# FeederShieldMega.net
KiCad netlist of a schematic drawn in EAGLE
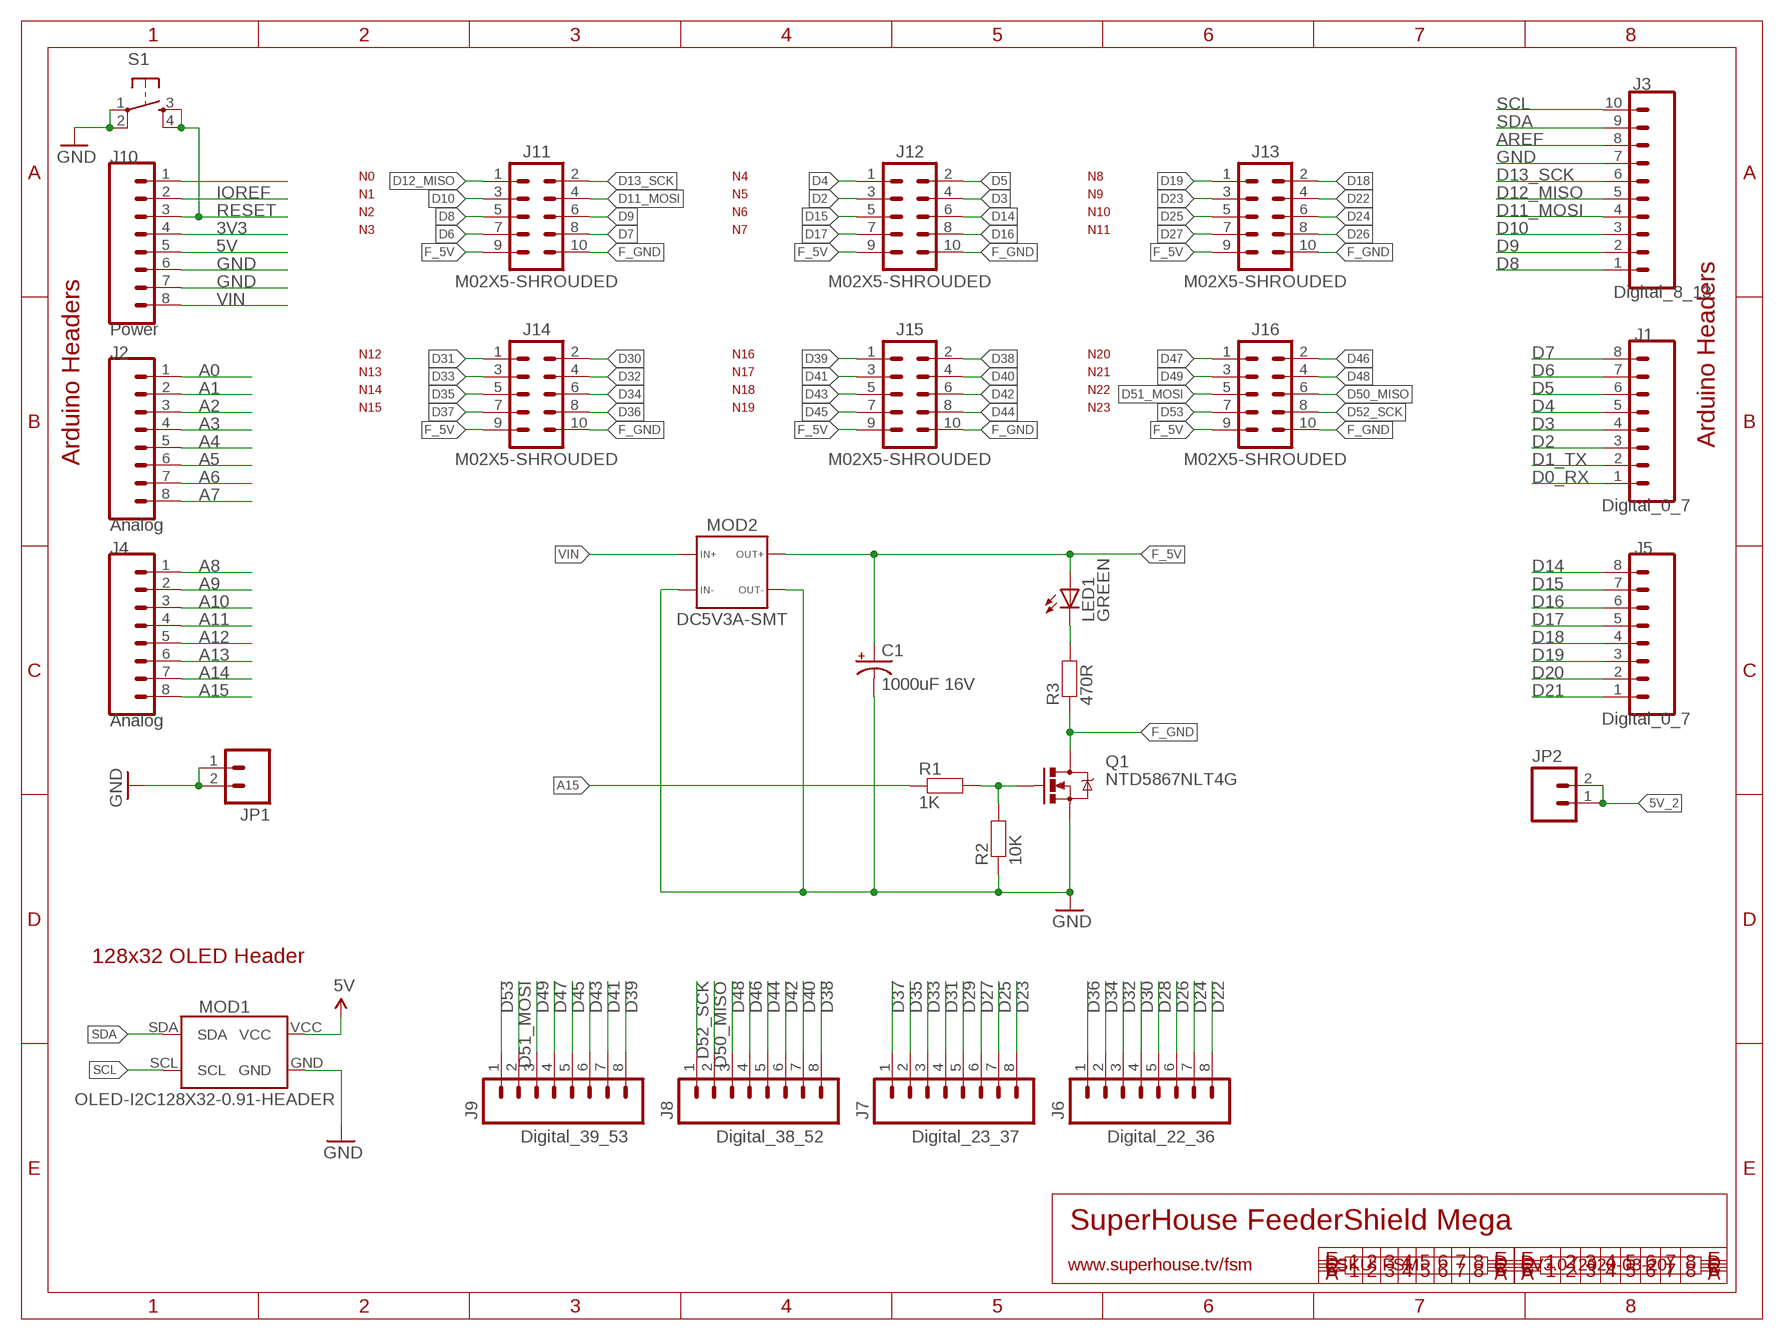
[diagram p0: schematic, sheet 1]

(export (version "E")
  (design (tool "Eeschema 10.0.6"))
  (components
    (comp (ref "C1")
      (value "1000uF 16V")
      (footprint "eagle-import:CPOL-RADIAL-5.08-10X18-FLAT")
      (libsource (lib "eagle-import") (part "CAP_POL-5.08-10X18-FLAT"))
    )
    (comp (ref "J1")
      (value "Digital_0_7")
      (footprint "eagle-import:1X08-P-BELOW")
      (libsource (lib "eagle-import") (part "M08-PIN-BELOW"))
    )
    (comp (ref "J2")
      (value "Analog")
      (footprint "eagle-import:1X08-P-BELOW")
      (libsource (lib "eagle-import") (part "M08-PIN-BELOW"))
    )
    (comp (ref "J3")
      (value "Digital_8_13")
      (footprint "eagle-import:1X10-P-BELOW")
      (libsource (lib "eagle-import") (part "M10-PIN-BELOW"))
    )
    (comp (ref "J4")
      (value "Analog")
      (footprint "eagle-import:1X08-P-BELOW")
      (libsource (lib "eagle-import") (part "M08-PIN-BELOW"))
    )
    (comp (ref "J5")
      (value "Digital_0_7")
      (footprint "eagle-import:1X08-P-BELOW")
      (libsource (lib "eagle-import") (part "M08-PIN-BELOW"))
    )
    (comp (ref "J6")
      (value "Digital_22_36")
      (footprint "eagle-import:1X08-P-BELOW")
      (libsource (lib "eagle-import") (part "M08-PIN-BELOW"))
    )
    (comp (ref "J7")
      (value "Digital_23_37")
      (footprint "eagle-import:1X08-P-BELOW")
      (libsource (lib "eagle-import") (part "M08-PIN-BELOW"))
    )
    (comp (ref "J8")
      (value "Digital_38_52")
      (footprint "eagle-import:1X08-P-BELOW")
      (libsource (lib "eagle-import") (part "M08-PIN-BELOW"))
    )
    (comp (ref "J9")
      (value "Digital_39_53")
      (footprint "eagle-import:1X08-P-BELOW")
      (libsource (lib "eagle-import") (part "M08-PIN-BELOW"))
    )
    (comp (ref "J10")
      (value "Power")
      (footprint "eagle-import:1X08-P-BELOW")
      (libsource (lib "eagle-import") (part "M08-PIN-BELOW"))
    )
    (comp (ref "J11")
      (value "M02X5-SHROUDED")
      (footprint "eagle-import:2X05-2.54-SHROUDED")
      (libsource (lib "eagle-import") (part "M02X5-SHROUDED"))
    )
    (comp (ref "J12")
      (value "M02X5-SHROUDED")
      (footprint "eagle-import:2X05-2.54-SHROUDED")
      (libsource (lib "eagle-import") (part "M02X5-SHROUDED"))
    )
    (comp (ref "J13")
      (value "M02X5-SHROUDED")
      (footprint "eagle-import:2X05-2.54-SHROUDED")
      (libsource (lib "eagle-import") (part "M02X5-SHROUDED"))
    )
    (comp (ref "J14")
      (value "M02X5-SHROUDED")
      (footprint "eagle-import:2X05-2.54-SHROUDED")
      (libsource (lib "eagle-import") (part "M02X5-SHROUDED"))
    )
    (comp (ref "J15")
      (value "M02X5-SHROUDED")
      (footprint "eagle-import:2X05-2.54-SHROUDED")
      (libsource (lib "eagle-import") (part "M02X5-SHROUDED"))
    )
    (comp (ref "J16")
      (value "M02X5-SHROUDED")
      (footprint "eagle-import:2X05-2.54-SHROUDED")
      (libsource (lib "eagle-import") (part "M02X5-SHROUDED"))
    )
    (comp (ref "JP1")
      (value "M02-PIN-BELOW")
      (footprint "eagle-import:1X02-P-BELOW")
      (libsource (lib "eagle-import") (part "M02-PIN-BELOW"))
    )
    (comp (ref "JP2")
      (value "M02-PIN-BELOW")
      (footprint "eagle-import:1X02-P-BELOW")
      (libsource (lib "eagle-import") (part "M02-PIN-BELOW"))
    )
    (comp (ref "LED1")
      (value "GREEN")
      (footprint "eagle-import:LED-0603")
      (libsource (lib "eagle-import") (part "LED0603"))
    )
    (comp (ref "MOD1")
      (value "OLED-I2C128X32-0.91-HEADER")
      (footprint "eagle-import:OLED-128X32-0.91-HEADER")
      (libsource (lib "eagle-import") (part "OLED-I2C128X32-0.91-HEADER"))
    )
    (comp (ref "MOD2")
      (value "DC5V3A-SMT")
      (footprint "eagle-import:DC5V3A-SMT")
      (libsource (lib "eagle-import") (part "DC5V3A-SMT"))
    )
    (comp (ref "Q1")
      (value "NTD5867NLT4G")
      (footprint "eagle-import:DPACK")
      (libsource (lib "eagle-import") (part "MOSFET-NCHANNEL-DPAK"))
    )
    (comp (ref "R1")
      (value "1K")
      (footprint "eagle-import:R0603")
      (libsource (lib "eagle-import") (part "RESISTOR0603"))
    )
    (comp (ref "R2")
      (value "10K")
      (footprint "eagle-import:R0603")
      (libsource (lib "eagle-import") (part "RESISTOR0603"))
    )
    (comp (ref "R3")
      (value "470R")
      (footprint "eagle-import:R0603")
      (libsource (lib "eagle-import") (part "RESISTOR0603"))
    )
    (comp (ref "S1")
      (value "TAC_SWITCH-PTH-6")
      (footprint "eagle-import:TACTILE-PTH-6MM")
      (libsource (lib "eagle-import") (part "TAC_SWITCH-PTH-6"))
    )
  )
  (nets
    (net (code "1") (name "/3V3") (class "Default")
      (node (ref "J10") (pin "4") (pinfunction "4_4") (pintype "passive"))
    )
    (net (code "2") (name "/A0") (class "Default")
      (node (ref "J2") (pin "1") (pinfunction "1_1") (pintype "passive"))
    )
    (net (code "3") (name "/A1") (class "Default")
      (node (ref "J2") (pin "2") (pinfunction "2_2") (pintype "passive"))
    )
    (net (code "4") (name "/A2") (class "Default")
      (node (ref "J2") (pin "3") (pinfunction "3_3") (pintype "passive"))
    )
    (net (code "5") (name "/A3") (class "Default")
      (node (ref "J2") (pin "4") (pinfunction "4_4") (pintype "passive"))
    )
    (net (code "6") (name "/A4") (class "Default")
      (node (ref "J2") (pin "5") (pinfunction "5_5") (pintype "passive"))
    )
    (net (code "7") (name "/A5") (class "Default")
      (node (ref "J2") (pin "6") (pinfunction "6_6") (pintype "passive"))
    )
    (net (code "8") (name "/A6") (class "Default")
      (node (ref "J2") (pin "7") (pinfunction "7_7") (pintype "passive"))
    )
    (net (code "9") (name "/A7") (class "Default")
      (node (ref "J2") (pin "8") (pinfunction "8_8") (pintype "passive"))
    )
    (net (code "10") (name "/A8") (class "Default")
      (node (ref "J4") (pin "1") (pinfunction "1_1") (pintype "passive"))
    )
    (net (code "11") (name "/A9") (class "Default")
      (node (ref "J4") (pin "2") (pinfunction "2_2") (pintype "passive"))
    )
    (net (code "12") (name "/A10") (class "Default")
      (node (ref "J4") (pin "3") (pinfunction "3_3") (pintype "passive"))
    )
    (net (code "13") (name "/A11") (class "Default")
      (node (ref "J4") (pin "4") (pinfunction "4_4") (pintype "passive"))
    )
    (net (code "14") (name "/A12") (class "Default")
      (node (ref "J4") (pin "5") (pinfunction "5_5") (pintype "passive"))
    )
    (net (code "15") (name "/A13") (class "Default")
      (node (ref "J4") (pin "6") (pinfunction "6_6") (pintype "passive"))
    )
    (net (code "16") (name "/A14") (class "Default")
      (node (ref "J4") (pin "7") (pinfunction "7_7") (pintype "passive"))
    )
    (net (code "17") (name "/AREF") (class "Default")
      (node (ref "J3") (pin "8") (pinfunction "8_8") (pintype "passive"))
    )
    (net (code "18") (name "/D0_RX") (class "Default")
      (node (ref "J1") (pin "1") (pinfunction "1_1") (pintype "passive"))
    )
    (net (code "19") (name "/D1_TX") (class "Default")
      (node (ref "J1") (pin "2") (pinfunction "2_2") (pintype "passive"))
    )
    (net (code "20") (name "/D20") (class "Default")
      (node (ref "J5") (pin "2") (pinfunction "2_2") (pintype "passive"))
    )
    (net (code "21") (name "/D21") (class "Default")
      (node (ref "J5") (pin "1") (pinfunction "1_1") (pintype "passive"))
    )
    (net (code "22") (name "/D28") (class "Default")
      (node (ref "J6") (pin "5") (pinfunction "5_5") (pintype "passive"))
    )
    (net (code "23") (name "/D29") (class "Default")
      (node (ref "J7") (pin "5") (pinfunction "5_5") (pintype "passive"))
    )
    (net (code "24") (name "/IOREF") (class "Default")
      (node (ref "J10") (pin "2") (pinfunction "2_2") (pintype "passive"))
    )
    (net (code "25") (name "/RESET") (class "Default")
      (node (ref "J10") (pin "3") (pinfunction "3_3") (pintype "passive"))
      (node (ref "S1") (pin "3") (pinfunction "3_3") (pintype "passive"))
      (node (ref "S1") (pin "4") (pinfunction "4_4") (pintype "passive"))
    )
    (net (code "26") (name "5V") (class "Default")
      (node (ref "J10") (pin "5") (pinfunction "5_5") (pintype "passive"))
      (node (ref "MOD1") (pin "VCC") (pinfunction "VCC_VCC") (pintype "bidirectional"))
    )
    (net (code "27") (name "5V_2") (class "Default")
      (node (ref "JP2") (pin "1") (pinfunction "1_1") (pintype "passive"))
      (node (ref "JP2") (pin "2") (pinfunction "2_2") (pintype "passive"))
    )
    (net (code "28") (name "A15") (class "Default")
      (node (ref "J4") (pin "8") (pinfunction "8_8") (pintype "passive"))
      (node (ref "R1") (pin "1") (pinfunction "1_1") (pintype "passive"))
    )
    (net (code "29") (name "D2") (class "Default")
      (node (ref "J1") (pin "3") (pinfunction "3_3") (pintype "passive"))
      (node (ref "J12") (pin "3") (pinfunction "3_3") (pintype "passive"))
    )
    (net (code "30") (name "D3") (class "Default")
      (node (ref "J1") (pin "4") (pinfunction "4_4") (pintype "passive"))
      (node (ref "J12") (pin "4") (pinfunction "4_4") (pintype "passive"))
    )
    (net (code "31") (name "D4") (class "Default")
      (node (ref "J1") (pin "5") (pinfunction "5_5") (pintype "passive"))
      (node (ref "J12") (pin "1") (pinfunction "1_1") (pintype "passive"))
    )
    (net (code "32") (name "D5") (class "Default")
      (node (ref "J1") (pin "6") (pinfunction "6_6") (pintype "passive"))
      (node (ref "J12") (pin "2") (pinfunction "2_2") (pintype "passive"))
    )
    (net (code "33") (name "D6") (class "Default")
      (node (ref "J1") (pin "7") (pinfunction "7_7") (pintype "passive"))
      (node (ref "J11") (pin "7") (pinfunction "7_7") (pintype "passive"))
    )
    (net (code "34") (name "D7") (class "Default")
      (node (ref "J1") (pin "8") (pinfunction "8_8") (pintype "passive"))
      (node (ref "J11") (pin "8") (pinfunction "8_8") (pintype "passive"))
    )
    (net (code "35") (name "D8") (class "Default")
      (node (ref "J11") (pin "5") (pinfunction "5_5") (pintype "passive"))
      (node (ref "J3") (pin "1") (pinfunction "1_1") (pintype "passive"))
    )
    (net (code "36") (name "D9") (class "Default")
      (node (ref "J11") (pin "6") (pinfunction "6_6") (pintype "passive"))
      (node (ref "J3") (pin "2") (pinfunction "2_2") (pintype "passive"))
    )
    (net (code "37") (name "D10") (class "Default")
      (node (ref "J11") (pin "3") (pinfunction "3_3") (pintype "passive"))
      (node (ref "J3") (pin "3") (pinfunction "3_3") (pintype "passive"))
    )
    (net (code "38") (name "D11_MOSI") (class "Default")
      (node (ref "J11") (pin "4") (pinfunction "4_4") (pintype "passive"))
      (node (ref "J3") (pin "4") (pinfunction "4_4") (pintype "passive"))
    )
    (net (code "39") (name "D12_MISO") (class "Default")
      (node (ref "J11") (pin "1") (pinfunction "1_1") (pintype "passive"))
      (node (ref "J3") (pin "5") (pinfunction "5_5") (pintype "passive"))
    )
    (net (code "40") (name "D13_SCK") (class "Default")
      (node (ref "J11") (pin "2") (pinfunction "2_2") (pintype "passive"))
      (node (ref "J3") (pin "6") (pinfunction "6_6") (pintype "passive"))
    )
    (net (code "41") (name "D14") (class "Default")
      (node (ref "J12") (pin "6") (pinfunction "6_6") (pintype "passive"))
      (node (ref "J5") (pin "8") (pinfunction "8_8") (pintype "passive"))
    )
    (net (code "42") (name "D15") (class "Default")
      (node (ref "J12") (pin "5") (pinfunction "5_5") (pintype "passive"))
      (node (ref "J5") (pin "7") (pinfunction "7_7") (pintype "passive"))
    )
    (net (code "43") (name "D16") (class "Default")
      (node (ref "J12") (pin "8") (pinfunction "8_8") (pintype "passive"))
      (node (ref "J5") (pin "6") (pinfunction "6_6") (pintype "passive"))
    )
    (net (code "44") (name "D17") (class "Default")
      (node (ref "J12") (pin "7") (pinfunction "7_7") (pintype "passive"))
      (node (ref "J5") (pin "5") (pinfunction "5_5") (pintype "passive"))
    )
    (net (code "45") (name "D18") (class "Default")
      (node (ref "J13") (pin "2") (pinfunction "2_2") (pintype "passive"))
      (node (ref "J5") (pin "4") (pinfunction "4_4") (pintype "passive"))
    )
    (net (code "46") (name "D19") (class "Default")
      (node (ref "J13") (pin "1") (pinfunction "1_1") (pintype "passive"))
      (node (ref "J5") (pin "3") (pinfunction "3_3") (pintype "passive"))
    )
    (net (code "47") (name "D22") (class "Default")
      (node (ref "J13") (pin "4") (pinfunction "4_4") (pintype "passive"))
      (node (ref "J6") (pin "8") (pinfunction "8_8") (pintype "passive"))
    )
    (net (code "48") (name "D23") (class "Default")
      (node (ref "J13") (pin "3") (pinfunction "3_3") (pintype "passive"))
      (node (ref "J7") (pin "8") (pinfunction "8_8") (pintype "passive"))
    )
    (net (code "49") (name "D24") (class "Default")
      (node (ref "J13") (pin "6") (pinfunction "6_6") (pintype "passive"))
      (node (ref "J6") (pin "7") (pinfunction "7_7") (pintype "passive"))
    )
    (net (code "50") (name "D25") (class "Default")
      (node (ref "J13") (pin "5") (pinfunction "5_5") (pintype "passive"))
      (node (ref "J7") (pin "7") (pinfunction "7_7") (pintype "passive"))
    )
    (net (code "51") (name "D26") (class "Default")
      (node (ref "J13") (pin "8") (pinfunction "8_8") (pintype "passive"))
      (node (ref "J6") (pin "6") (pinfunction "6_6") (pintype "passive"))
    )
    (net (code "52") (name "D27") (class "Default")
      (node (ref "J13") (pin "7") (pinfunction "7_7") (pintype "passive"))
      (node (ref "J7") (pin "6") (pinfunction "6_6") (pintype "passive"))
    )
    (net (code "53") (name "D30") (class "Default")
      (node (ref "J14") (pin "2") (pinfunction "2_2") (pintype "passive"))
      (node (ref "J6") (pin "4") (pinfunction "4_4") (pintype "passive"))
    )
    (net (code "54") (name "D31") (class "Default")
      (node (ref "J14") (pin "1") (pinfunction "1_1") (pintype "passive"))
      (node (ref "J7") (pin "4") (pinfunction "4_4") (pintype "passive"))
    )
    (net (code "55") (name "D32") (class "Default")
      (node (ref "J14") (pin "4") (pinfunction "4_4") (pintype "passive"))
      (node (ref "J6") (pin "3") (pinfunction "3_3") (pintype "passive"))
    )
    (net (code "56") (name "D33") (class "Default")
      (node (ref "J14") (pin "3") (pinfunction "3_3") (pintype "passive"))
      (node (ref "J7") (pin "3") (pinfunction "3_3") (pintype "passive"))
    )
    (net (code "57") (name "D34") (class "Default")
      (node (ref "J14") (pin "6") (pinfunction "6_6") (pintype "passive"))
      (node (ref "J6") (pin "2") (pinfunction "2_2") (pintype "passive"))
    )
    (net (code "58") (name "D35") (class "Default")
      (node (ref "J14") (pin "5") (pinfunction "5_5") (pintype "passive"))
      (node (ref "J7") (pin "2") (pinfunction "2_2") (pintype "passive"))
    )
    (net (code "59") (name "D36") (class "Default")
      (node (ref "J14") (pin "8") (pinfunction "8_8") (pintype "passive"))
      (node (ref "J6") (pin "1") (pinfunction "1_1") (pintype "passive"))
    )
    (net (code "60") (name "D37") (class "Default")
      (node (ref "J14") (pin "7") (pinfunction "7_7") (pintype "passive"))
      (node (ref "J7") (pin "1") (pinfunction "1_1") (pintype "passive"))
    )
    (net (code "61") (name "D38") (class "Default")
      (node (ref "J15") (pin "2") (pinfunction "2_2") (pintype "passive"))
      (node (ref "J8") (pin "8") (pinfunction "8_8") (pintype "passive"))
    )
    (net (code "62") (name "D39") (class "Default")
      (node (ref "J15") (pin "1") (pinfunction "1_1") (pintype "passive"))
      (node (ref "J9") (pin "8") (pinfunction "8_8") (pintype "passive"))
    )
    (net (code "63") (name "D40") (class "Default")
      (node (ref "J15") (pin "4") (pinfunction "4_4") (pintype "passive"))
      (node (ref "J8") (pin "7") (pinfunction "7_7") (pintype "passive"))
    )
    (net (code "64") (name "D41") (class "Default")
      (node (ref "J15") (pin "3") (pinfunction "3_3") (pintype "passive"))
      (node (ref "J9") (pin "7") (pinfunction "7_7") (pintype "passive"))
    )
    (net (code "65") (name "D42") (class "Default")
      (node (ref "J15") (pin "6") (pinfunction "6_6") (pintype "passive"))
      (node (ref "J8") (pin "6") (pinfunction "6_6") (pintype "passive"))
    )
    (net (code "66") (name "D43") (class "Default")
      (node (ref "J15") (pin "5") (pinfunction "5_5") (pintype "passive"))
      (node (ref "J9") (pin "6") (pinfunction "6_6") (pintype "passive"))
    )
    (net (code "67") (name "D44") (class "Default")
      (node (ref "J15") (pin "8") (pinfunction "8_8") (pintype "passive"))
      (node (ref "J8") (pin "5") (pinfunction "5_5") (pintype "passive"))
    )
    (net (code "68") (name "D45") (class "Default")
      (node (ref "J15") (pin "7") (pinfunction "7_7") (pintype "passive"))
      (node (ref "J9") (pin "5") (pinfunction "5_5") (pintype "passive"))
    )
    (net (code "69") (name "D46") (class "Default")
      (node (ref "J16") (pin "2") (pinfunction "2_2") (pintype "passive"))
      (node (ref "J8") (pin "4") (pinfunction "4_4") (pintype "passive"))
    )
    (net (code "70") (name "D47") (class "Default")
      (node (ref "J16") (pin "1") (pinfunction "1_1") (pintype "passive"))
      (node (ref "J9") (pin "4") (pinfunction "4_4") (pintype "passive"))
    )
    (net (code "71") (name "D48") (class "Default")
      (node (ref "J16") (pin "4") (pinfunction "4_4") (pintype "passive"))
      (node (ref "J8") (pin "3") (pinfunction "3_3") (pintype "passive"))
    )
    (net (code "72") (name "D49") (class "Default")
      (node (ref "J16") (pin "3") (pinfunction "3_3") (pintype "passive"))
      (node (ref "J9") (pin "3") (pinfunction "3_3") (pintype "passive"))
    )
    (net (code "73") (name "D50_MISO") (class "Default")
      (node (ref "J16") (pin "6") (pinfunction "6_6") (pintype "passive"))
      (node (ref "J8") (pin "2") (pinfunction "2_2") (pintype "passive"))
    )
    (net (code "74") (name "D51_MOSI") (class "Default")
      (node (ref "J16") (pin "5") (pinfunction "5_5") (pintype "passive"))
      (node (ref "J9") (pin "2") (pinfunction "2_2") (pintype "passive"))
    )
    (net (code "75") (name "D52_SCK") (class "Default")
      (node (ref "J16") (pin "8") (pinfunction "8_8") (pintype "passive"))
      (node (ref "J8") (pin "1") (pinfunction "1_1") (pintype "passive"))
    )
    (net (code "76") (name "D53") (class "Default")
      (node (ref "J16") (pin "7") (pinfunction "7_7") (pintype "passive"))
      (node (ref "J9") (pin "1") (pinfunction "1_1") (pintype "passive"))
    )
    (net (code "77") (name "F_5V") (class "Default")
      (node (ref "C1") (pin "1") (pinfunction "+_1") (pintype "passive"))
      (node (ref "J11") (pin "9") (pinfunction "9_9") (pintype "passive"))
      (node (ref "J12") (pin "9") (pinfunction "9_9") (pintype "passive"))
      (node (ref "J13") (pin "9") (pinfunction "9_9") (pintype "passive"))
      (node (ref "J14") (pin "9") (pinfunction "9_9") (pintype "passive"))
      (node (ref "J15") (pin "9") (pinfunction "9_9") (pintype "passive"))
      (node (ref "J16") (pin "9") (pinfunction "9_9") (pintype "passive"))
      (node (ref "LED1") (pin "A") (pinfunction "A_A") (pintype "passive"))
      (node (ref "MOD2") (pin "3A") (pinfunction "3_3A") (pintype "bidirectional"))
      (node (ref "MOD2") (pin "3B") (pinfunction "3_3B") (pintype "bidirectional"))
    )
    (net (code "78") (name "F_GND") (class "Default")
      (node (ref "J11") (pin "10") (pinfunction "10_10") (pintype "passive"))
      (node (ref "J12") (pin "10") (pinfunction "10_10") (pintype "passive"))
      (node (ref "J13") (pin "10") (pinfunction "10_10") (pintype "passive"))
      (node (ref "J14") (pin "10") (pinfunction "10_10") (pintype "passive"))
      (node (ref "J15") (pin "10") (pinfunction "10_10") (pintype "passive"))
      (node (ref "J16") (pin "10") (pinfunction "10_10") (pintype "passive"))
      (node (ref "Q1") (pin "2") (pinfunction "D_2") (pintype "passive"))
      (node (ref "R3") (pin "1") (pinfunction "1_1") (pintype "passive"))
    )
    (net (code "79") (name "GND") (class "Default")
      (node (ref "C1") (pin "2") (pinfunction "-_2") (pintype "passive"))
      (node (ref "J10") (pin "6") (pinfunction "6_6") (pintype "passive"))
      (node (ref "J10") (pin "7") (pinfunction "7_7") (pintype "passive"))
      (node (ref "J3") (pin "7") (pinfunction "7_7") (pintype "passive"))
      (node (ref "JP1") (pin "1") (pinfunction "1_1") (pintype "passive"))
      (node (ref "JP1") (pin "2") (pinfunction "2_2") (pintype "passive"))
      (node (ref "MOD1") (pin "GND") (pinfunction "GND_GND") (pintype "bidirectional"))
      (node (ref "MOD2") (pin "1A") (pinfunction "1_1A") (pintype "bidirectional"))
      (node (ref "MOD2") (pin "1B") (pinfunction "1_1B") (pintype "bidirectional"))
      (node (ref "MOD2") (pin "4A") (pinfunction "4_4A") (pintype "bidirectional"))
      (node (ref "MOD2") (pin "4B") (pinfunction "4_4B") (pintype "bidirectional"))
      (node (ref "Q1") (pin "3") (pinfunction "S_3") (pintype "passive"))
      (node (ref "R2") (pin "1") (pinfunction "1_1") (pintype "passive"))
      (node (ref "S1") (pin "1") (pinfunction "1_1") (pintype "passive"))
      (node (ref "S1") (pin "2") (pinfunction "2_2") (pintype "passive"))
    )
    (net (code "80") (name "Net-(LED1-PadC)") (class "Default")
      (node (ref "LED1") (pin "C") (pinfunction "C_C") (pintype "passive"))
      (node (ref "R3") (pin "2") (pinfunction "2_2") (pintype "passive"))
    )
    (net (code "81") (name "Net-(Q1-G)") (class "Default")
      (node (ref "Q1") (pin "1") (pinfunction "G_1") (pintype "passive"))
      (node (ref "R1") (pin "2") (pinfunction "2_2") (pintype "passive"))
      (node (ref "R2") (pin "2") (pinfunction "2_2") (pintype "passive"))
    )
    (net (code "82") (name "SCL") (class "Default")
      (node (ref "J3") (pin "10") (pinfunction "10_10") (pintype "passive"))
      (node (ref "MOD1") (pin "SCL") (pinfunction "SCL_SCL") (pintype "bidirectional"))
    )
    (net (code "83") (name "SDA") (class "Default")
      (node (ref "J3") (pin "9") (pinfunction "9_9") (pintype "passive"))
      (node (ref "MOD1") (pin "SDA") (pinfunction "SDA_SDA") (pintype "bidirectional"))
    )
    (net (code "84") (name "VIN") (class "Default")
      (node (ref "J10") (pin "8") (pinfunction "8_8") (pintype "passive"))
      (node (ref "MOD2") (pin "2A") (pinfunction "2_2A") (pintype "bidirectional"))
      (node (ref "MOD2") (pin "2B") (pinfunction "2_2B") (pintype "bidirectional"))
    )
    (net (code "85") (name "unconnected-(J10-Pad1)") (class "Default")
      (node (ref "J10") (pin "1") (pinfunction "1_1") (pintype "passive"))
    )
  )
)
